# water_heater.net
KiCad netlist of a schematic drawn in EAGLE
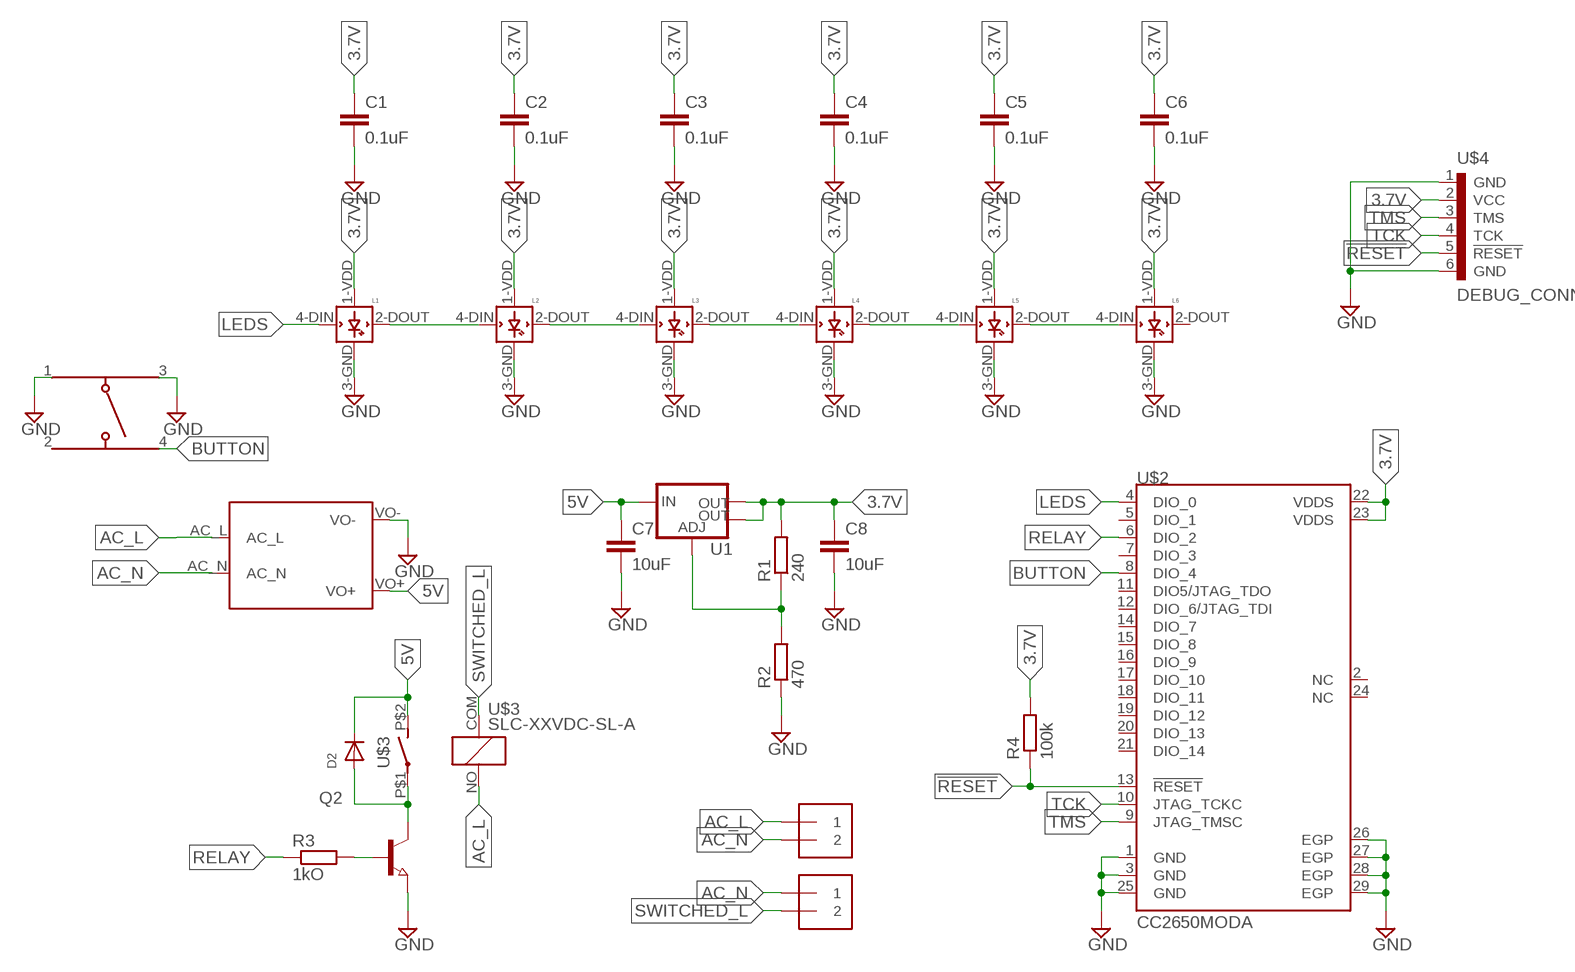
[diagram p0: schematic, sheet 1]

(export (version "E")
  (design (tool "Eeschema 10.0.6"))
  (components
    (comp (ref "C1")
      (value "0.1uF")
      (footprint "eagle-import:0402")
      (libsource (lib "eagle-import") (part "CAPACITOR_0402"))
    )
    (comp (ref "C2")
      (value "0.1uF")
      (footprint "eagle-import:0402")
      (libsource (lib "eagle-import") (part "CAPACITOR_0402"))
    )
    (comp (ref "C3")
      (value "0.1uF")
      (footprint "eagle-import:0402")
      (libsource (lib "eagle-import") (part "CAPACITOR_0402"))
    )
    (comp (ref "C4")
      (value "0.1uF")
      (footprint "eagle-import:0402")
      (libsource (lib "eagle-import") (part "CAPACITOR_0402"))
    )
    (comp (ref "C5")
      (value "0.1uF")
      (footprint "eagle-import:0402")
      (libsource (lib "eagle-import") (part "CAPACITOR_0402"))
    )
    (comp (ref "C6")
      (value "0.1uF")
      (footprint "eagle-import:0402")
      (libsource (lib "eagle-import") (part "CAPACITOR_0402"))
    )
    (comp (ref "C7")
      (value "10uF")
      (footprint "eagle-import:0402")
      (libsource (lib "eagle-import") (part "CAPACITOR_0402"))
    )
    (comp (ref "C8")
      (value "10uF")
      (footprint "eagle-import:0402")
      (libsource (lib "eagle-import") (part "CAPACITOR_0402"))
    )
    (comp (ref "D2")
      (value "DIODESOD-123")
      (footprint "eagle-import:SOD-123")
      (libsource (lib "eagle-import") (part "DIODESOD-123"))
    )
    (comp (ref "L1")
      (value "WS2812B")
      (footprint "eagle-import:WS2812B")
      (libsource (lib "eagle-import") (part "WS2812B"))
    )
    (comp (ref "L2")
      (value "WS2812B")
      (footprint "eagle-import:WS2812B")
      (libsource (lib "eagle-import") (part "WS2812B"))
    )
    (comp (ref "L3")
      (value "WS2812B")
      (footprint "eagle-import:WS2812B")
      (libsource (lib "eagle-import") (part "WS2812B"))
    )
    (comp (ref "L4")
      (value "WS2812B")
      (footprint "eagle-import:WS2812B")
      (libsource (lib "eagle-import") (part "WS2812B"))
    )
    (comp (ref "L5")
      (value "WS2812B")
      (footprint "eagle-import:WS2812B")
      (libsource (lib "eagle-import") (part "WS2812B"))
    )
    (comp (ref "L6")
      (value "WS2812B")
      (footprint "eagle-import:WS2812B")
      (libsource (lib "eagle-import") (part "WS2812B"))
    )
    (comp (ref "Q2")
      (value "NPN-TRANSISTOR_SOT23")
      (footprint "eagle-import:SOT23")
      (libsource (lib "eagle-import") (part "NPN-TRANSISTOR_SOT23"))
    )
    (comp (ref "R1")
      (value "240")
      (footprint "eagle-import:0402")
      (libsource (lib "eagle-import") (part "RESISTOR_0402"))
    )
    (comp (ref "R2")
      (value "470")
      (footprint "eagle-import:0402")
      (libsource (lib "eagle-import") (part "RESISTOR_0402"))
    )
    (comp (ref "R3")
      (value "1kO")
      (footprint "eagle-import:0402")
      (libsource (lib "eagle-import") (part "RESISTOR_0402"))
    )
    (comp (ref "R4")
      (value "100k")
      (footprint "eagle-import:0402")
      (libsource (lib "eagle-import") (part "RESISTOR_0402"))
    )
    (comp (ref "U$1")
      (value "HLK-PM01")
      (footprint "eagle-import:HLK-PM01")
      (libsource (lib "eagle-import") (part "HLK-PM01"))
    )
    (comp (ref "U$2")
      (value "CC2650MODA")
      (footprint "eagle-import:CC2650MODA")
      (libsource (lib "eagle-import") (part "CC2650MODA"))
    )
    (comp (ref "U$3")
      (value "SLC-XXVDC-SL-A")
      (footprint "eagle-import:SLC-1_FORM_A")
      (libsource (lib "eagle-import") (part "SLC-XXVDC-SL-A"))
    )
    (comp (ref "U$4")
      (value "DEBUG_CONN")
      (footprint "eagle-import:DEBUG_CONN")
      (libsource (lib "eagle-import") (part "DEBUG_CONN"))
    )
    (comp (ref "U$5")
      (value "CTS222AM")
      (footprint "eagle-import:CTS222AM")
      (libsource (lib "eagle-import") (part "CTS222AM"))
    )
    (comp (ref "U$8")
      (value "1X2-5MM-RIGHT")
      (footprint "eagle-import:1X2-5MM-RIGHT")
      (libsource (lib "eagle-import") (part "1X2-5MM-RIGHT"))
    )
    (comp (ref "U$9")
      (value "1X2-5MM-RIGHT")
      (footprint "eagle-import:1X2-5MM-RIGHT")
      (libsource (lib "eagle-import") (part "1X2-5MM-RIGHT"))
    )
    (comp (ref "U1")
      (value "V_REG_LM1117SOT223")
      (footprint "eagle-import:SOT223")
      (libsource (lib "eagle-import") (part "V_REG_LM1117SOT223"))
    )
  )
  (nets
    (net (code "1") (name "/~{RESET}") (class "Default")
      (node (ref "R4") (pin "1") (pinfunction "1_1") (pintype "passive"))
      (node (ref "U$2") (pin "13") (pinfunction "~{RESET}_13") (pintype "bidirectional"))
      (node (ref "U$4") (pin "5") (pinfunction "~{RESET}_5") (pintype "bidirectional"))
    )
    (net (code "2") (name "3.7V") (class "Default")
      (node (ref "C1") (pin "1") (pinfunction "1_1") (pintype "passive"))
      (node (ref "C2") (pin "1") (pinfunction "1_1") (pintype "passive"))
      (node (ref "C3") (pin "1") (pinfunction "1_1") (pintype "passive"))
      (node (ref "C4") (pin "1") (pinfunction "1_1") (pintype "passive"))
      (node (ref "C5") (pin "1") (pinfunction "1_1") (pintype "passive"))
      (node (ref "C6") (pin "1") (pinfunction "1_1") (pintype "passive"))
      (node (ref "C8") (pin "1") (pinfunction "1_1") (pintype "passive"))
      (node (ref "L1") (pin "1-VDD") (pinfunction "VDD_1-VDD") (pintype "bidirectional"))
      (node (ref "L2") (pin "1-VDD") (pinfunction "VDD_1-VDD") (pintype "bidirectional"))
      (node (ref "L3") (pin "1-VDD") (pinfunction "VDD_1-VDD") (pintype "bidirectional"))
      (node (ref "L4") (pin "1-VDD") (pinfunction "VDD_1-VDD") (pintype "bidirectional"))
      (node (ref "L5") (pin "1-VDD") (pinfunction "VDD_1-VDD") (pintype "bidirectional"))
      (node (ref "L6") (pin "1-VDD") (pinfunction "VDD_1-VDD") (pintype "bidirectional"))
      (node (ref "R1") (pin "2") (pinfunction "2_2") (pintype "passive"))
      (node (ref "R4") (pin "2") (pinfunction "2_2") (pintype "passive"))
      (node (ref "U$2") (pin "22") (pinfunction "VDDS_22") (pintype "power_in"))
      (node (ref "U$2") (pin "23") (pinfunction "VDDS_23") (pintype "power_in"))
      (node (ref "U$4") (pin "2") (pinfunction "VCC_2") (pintype "bidirectional"))
      (node (ref "U1") (pin "2") (pinfunction "OUT_2") (pintype "output"))
      (node (ref "U1") (pin "4") (pinfunction "OUT_4") (pintype "output"))
    )
    (net (code "3") (name "5V") (class "Default")
      (node (ref "C7") (pin "1") (pinfunction "1_1") (pintype "passive"))
      (node (ref "D2") (pin "C") (pinfunction "C_C") (pintype "passive"))
      (node (ref "U$1") (pin "VO+") (pinfunction "VO+_VO+") (pintype "output"))
      (node (ref "U$3") (pin "P$2") (pinfunction "S_P$2") (pintype "passive"))
      (node (ref "U1") (pin "3") (pinfunction "IN_3") (pintype "input"))
    )
    (net (code "4") (name "AC_L") (class "Default")
      (node (ref "U$1") (pin "AC_L") (pinfunction "AC_L_AC_L") (pintype "input"))
      (node (ref "U$3") (pin "NO") (pinfunction "2_NO") (pintype "passive"))
      (node (ref "U$8") (pin "1") (pinfunction "1_1") (pintype "passive"))
    )
    (net (code "5") (name "AC_N") (class "Default")
      (node (ref "U$1") (pin "AC_N") (pinfunction "AC_N_AC_N") (pintype "input"))
      (node (ref "U$8") (pin "2") (pinfunction "2_2") (pintype "passive"))
      (node (ref "U$9") (pin "1") (pinfunction "1_1") (pintype "passive"))
    )
    (net (code "6") (name "BUTTON") (class "Default")
      (node (ref "U$2") (pin "8") (pinfunction "DIO_4_8") (pintype "bidirectional"))
      (node (ref "U$5") (pin "4") (pinfunction "4_4") (pintype "bidirectional"))
    )
    (net (code "7") (name "GND") (class "Default")
      (node (ref "C1") (pin "2") (pinfunction "2_2") (pintype "passive"))
      (node (ref "C2") (pin "2") (pinfunction "2_2") (pintype "passive"))
      (node (ref "C3") (pin "2") (pinfunction "2_2") (pintype "passive"))
      (node (ref "C4") (pin "2") (pinfunction "2_2") (pintype "passive"))
      (node (ref "C5") (pin "2") (pinfunction "2_2") (pintype "passive"))
      (node (ref "C6") (pin "2") (pinfunction "2_2") (pintype "passive"))
      (node (ref "C7") (pin "2") (pinfunction "2_2") (pintype "passive"))
      (node (ref "C8") (pin "2") (pinfunction "2_2") (pintype "passive"))
      (node (ref "L1") (pin "3-GND") (pinfunction "GND_3-GND") (pintype "bidirectional"))
      (node (ref "L2") (pin "3-GND") (pinfunction "GND_3-GND") (pintype "bidirectional"))
      (node (ref "L3") (pin "3-GND") (pinfunction "GND_3-GND") (pintype "bidirectional"))
      (node (ref "L4") (pin "3-GND") (pinfunction "GND_3-GND") (pintype "bidirectional"))
      (node (ref "L5") (pin "3-GND") (pinfunction "GND_3-GND") (pintype "bidirectional"))
      (node (ref "L6") (pin "3-GND") (pinfunction "GND_3-GND") (pintype "bidirectional"))
      (node (ref "Q2") (pin "2") (pinfunction "E_2") (pintype "passive"))
      (node (ref "R2") (pin "1") (pinfunction "1_1") (pintype "passive"))
      (node (ref "U$1") (pin "VO-") (pinfunction "VO-_VO-") (pintype "output"))
      (node (ref "U$2") (pin "1") (pinfunction "GND_1") (pintype "power_in"))
      (node (ref "U$2") (pin "25") (pinfunction "GND_25") (pintype "power_in"))
      (node (ref "U$2") (pin "26") (pinfunction "EGP_26") (pintype "power_in"))
      (node (ref "U$2") (pin "27") (pinfunction "EGP_27") (pintype "power_in"))
      (node (ref "U$2") (pin "28") (pinfunction "EGP_28") (pintype "power_in"))
      (node (ref "U$2") (pin "29") (pinfunction "EGP_29") (pintype "power_in"))
      (node (ref "U$2") (pin "3") (pinfunction "GND_3") (pintype "power_in"))
      (node (ref "U$4") (pin "1") (pinfunction "GND_1") (pintype "bidirectional"))
      (node (ref "U$4") (pin "6") (pinfunction "GND_6") (pintype "bidirectional"))
      (node (ref "U$5") (pin "1") (pinfunction "1_1") (pintype "bidirectional"))
      (node (ref "U$5") (pin "3") (pinfunction "3_3") (pintype "bidirectional"))
    )
    (net (code "8") (name "LEDS") (class "Default")
      (node (ref "L1") (pin "4-DIN") (pinfunction "DIN_4-DIN") (pintype "input"))
      (node (ref "U$2") (pin "4") (pinfunction "DIO_0_4") (pintype "bidirectional"))
    )
    (net (code "9") (name "Net-(L1-DOUT)") (class "Default")
      (node (ref "L1") (pin "2-DOUT") (pinfunction "DOUT_2-DOUT") (pintype "output"))
      (node (ref "L2") (pin "4-DIN") (pinfunction "DIN_4-DIN") (pintype "input"))
    )
    (net (code "10") (name "Net-(L2-DOUT)") (class "Default")
      (node (ref "L2") (pin "2-DOUT") (pinfunction "DOUT_2-DOUT") (pintype "output"))
      (node (ref "L3") (pin "4-DIN") (pinfunction "DIN_4-DIN") (pintype "input"))
    )
    (net (code "11") (name "Net-(L3-DOUT)") (class "Default")
      (node (ref "L3") (pin "2-DOUT") (pinfunction "DOUT_2-DOUT") (pintype "output"))
      (node (ref "L4") (pin "4-DIN") (pinfunction "DIN_4-DIN") (pintype "input"))
    )
    (net (code "12") (name "Net-(L4-DOUT)") (class "Default")
      (node (ref "L4") (pin "2-DOUT") (pinfunction "DOUT_2-DOUT") (pintype "output"))
      (node (ref "L5") (pin "4-DIN") (pinfunction "DIN_4-DIN") (pintype "input"))
    )
    (net (code "13") (name "Net-(L5-DOUT)") (class "Default")
      (node (ref "L5") (pin "2-DOUT") (pinfunction "DOUT_2-DOUT") (pintype "output"))
      (node (ref "L6") (pin "4-DIN") (pinfunction "DIN_4-DIN") (pintype "input"))
    )
    (net (code "14") (name "Net-(Q2-B)") (class "Default")
      (node (ref "Q2") (pin "1") (pinfunction "B_1") (pintype "passive"))
      (node (ref "R3") (pin "2") (pinfunction "2_2") (pintype "passive"))
    )
    (net (code "15") (name "Net-(Q2-C)") (class "Default")
      (node (ref "D2") (pin "A") (pinfunction "A_A") (pintype "passive"))
      (node (ref "Q2") (pin "3") (pinfunction "C_3") (pintype "passive"))
      (node (ref "U$3") (pin "P$1") (pinfunction "P_P$1") (pintype "passive"))
    )
    (net (code "16") (name "Net-(U1-ADJ)") (class "Default")
      (node (ref "R1") (pin "1") (pinfunction "1_1") (pintype "passive"))
      (node (ref "R2") (pin "2") (pinfunction "2_2") (pintype "passive"))
      (node (ref "U1") (pin "1") (pinfunction "ADJ_1") (pintype "input"))
    )
    (net (code "17") (name "RELAY") (class "Default")
      (node (ref "R3") (pin "1") (pinfunction "1_1") (pintype "passive"))
      (node (ref "U$2") (pin "6") (pinfunction "DIO_2_6") (pintype "bidirectional"))
    )
    (net (code "18") (name "SWITCHED_L") (class "Default")
      (node (ref "U$3") (pin "COM") (pinfunction "1_COM") (pintype "passive"))
      (node (ref "U$9") (pin "2") (pinfunction "2_2") (pintype "passive"))
    )
    (net (code "19") (name "TCK") (class "Default")
      (node (ref "U$2") (pin "10") (pinfunction "JTAG_TCKC_10") (pintype "bidirectional"))
      (node (ref "U$4") (pin "4") (pinfunction "TCK_4") (pintype "bidirectional"))
    )
    (net (code "20") (name "TMS") (class "Default")
      (node (ref "U$2") (pin "9") (pinfunction "JTAG_TMSC_9") (pintype "bidirectional"))
      (node (ref "U$4") (pin "3") (pinfunction "TMS_3") (pintype "bidirectional"))
    )
    (net (code "21") (name "unconnected-(L6-DOUT-Pad2-DOUT)") (class "Default")
      (node (ref "L6") (pin "2-DOUT") (pinfunction "DOUT_2-DOUT") (pintype "output"))
    )
    (net (code "22") (name "unconnected-(U$2-DIO5{slash}JTAG_TDO-Pad11)") (class "Default")
      (node (ref "U$2") (pin "11") (pinfunction "DIO5/JTAG_TDO_11") (pintype "bidirectional"))
    )
    (net (code "23") (name "unconnected-(U$2-DIO_1-Pad5)") (class "Default")
      (node (ref "U$2") (pin "5") (pinfunction "DIO_1_5") (pintype "bidirectional"))
    )
    (net (code "24") (name "unconnected-(U$2-DIO_3-Pad7)") (class "Default")
      (node (ref "U$2") (pin "7") (pinfunction "DIO_3_7") (pintype "bidirectional"))
    )
    (net (code "25") (name "unconnected-(U$2-DIO_6{slash}JTAG_TDI-Pad12)") (class "Default")
      (node (ref "U$2") (pin "12") (pinfunction "DIO_6/JTAG_TDI_12") (pintype "bidirectional"))
    )
    (net (code "26") (name "unconnected-(U$2-DIO_7-Pad14)") (class "Default")
      (node (ref "U$2") (pin "14") (pinfunction "DIO_7_14") (pintype "bidirectional"))
    )
    (net (code "27") (name "unconnected-(U$2-DIO_8-Pad15)") (class "Default")
      (node (ref "U$2") (pin "15") (pinfunction "DIO_8_15") (pintype "bidirectional"))
    )
    (net (code "28") (name "unconnected-(U$2-DIO_9-Pad16)") (class "Default")
      (node (ref "U$2") (pin "16") (pinfunction "DIO_9_16") (pintype "bidirectional"))
    )
    (net (code "29") (name "unconnected-(U$2-DIO_10-Pad17)") (class "Default")
      (node (ref "U$2") (pin "17") (pinfunction "DIO_10_17") (pintype "bidirectional"))
    )
    (net (code "30") (name "unconnected-(U$2-DIO_11-Pad18)") (class "Default")
      (node (ref "U$2") (pin "18") (pinfunction "DIO_11_18") (pintype "bidirectional"))
    )
    (net (code "31") (name "unconnected-(U$2-DIO_12-Pad19)") (class "Default")
      (node (ref "U$2") (pin "19") (pinfunction "DIO_12_19") (pintype "bidirectional"))
    )
    (net (code "32") (name "unconnected-(U$2-DIO_13-Pad20)") (class "Default")
      (node (ref "U$2") (pin "20") (pinfunction "DIO_13_20") (pintype "bidirectional"))
    )
    (net (code "33") (name "unconnected-(U$2-DIO_14-Pad21)") (class "Default")
      (node (ref "U$2") (pin "21") (pinfunction "DIO_14_21") (pintype "bidirectional"))
    )
    (net (code "34") (name "unconnected-(U$2-NC-Pad2)") (class "Default")
      (node (ref "U$2") (pin "2") (pinfunction "NC_2") (pintype "no_connect"))
    )
    (net (code "35") (name "unconnected-(U$2-NC-Pad24)") (class "Default")
      (node (ref "U$2") (pin "24") (pinfunction "NC_24") (pintype "no_connect"))
    )
    (net (code "36") (name "unconnected-(U$5-Pad2)") (class "Default")
      (node (ref "U$5") (pin "2") (pinfunction "2_2") (pintype "bidirectional"))
    )
  )
)
